# AMP_1_0.net
KiCad netlist of a schematic drawn in EAGLE
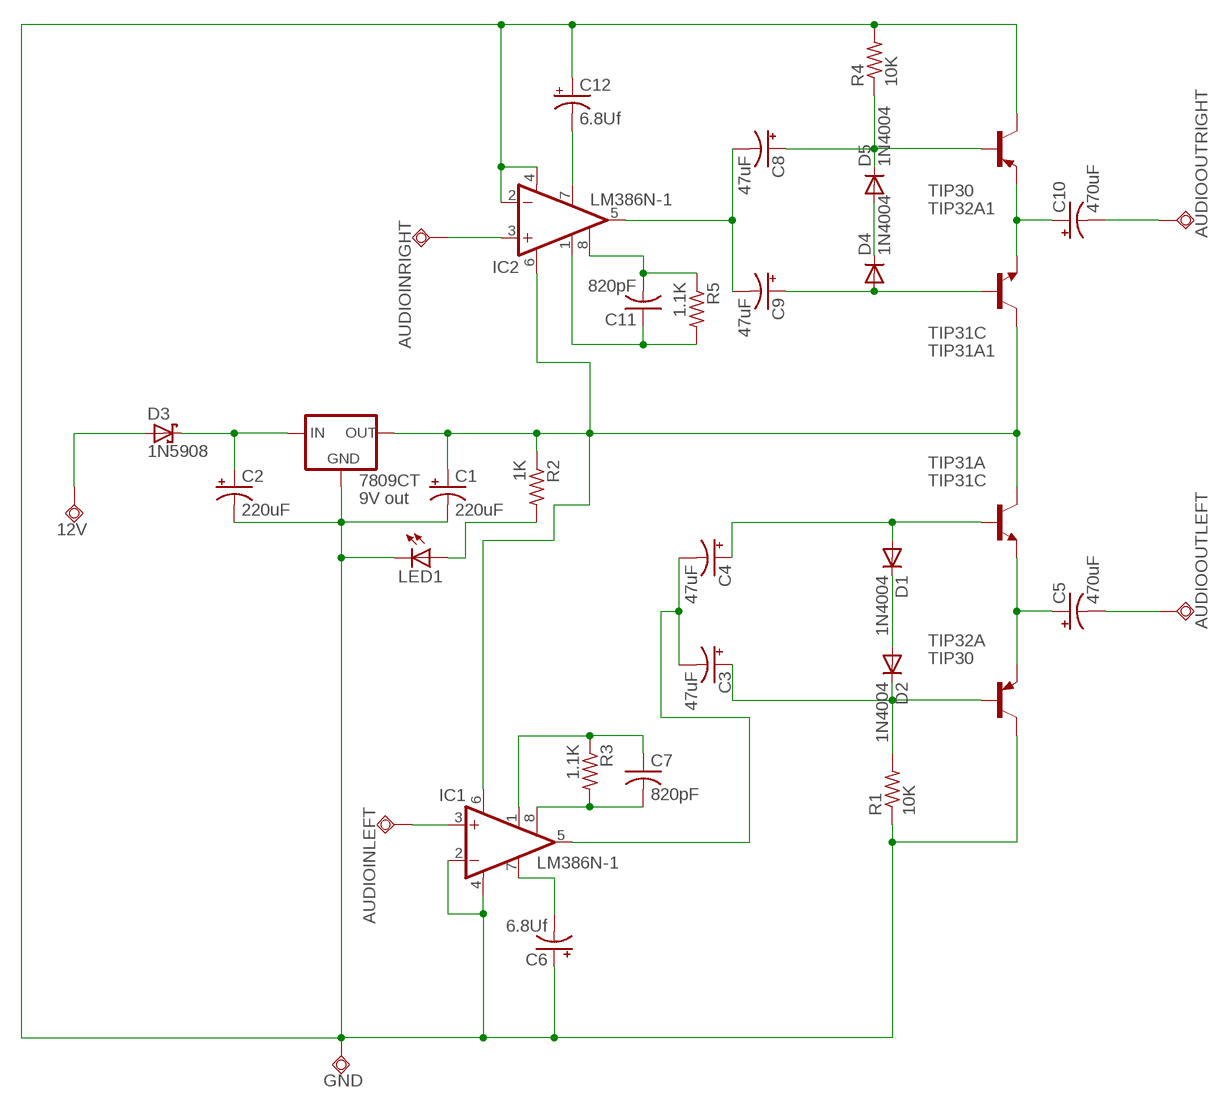
[diagram p0: schematic, sheet 1]

(export (version "E")
  (design (tool "Eeschema 10.0.6"))
  (components
    (comp (ref "12V")
      (value "TPSQPAD1-20")
      (footprint "eagle-import:P1-20")
      (libsource (lib "eagle-import") (part "TPSQPAD1-20"))
    )
    (comp (ref "7809CT")
      (value "9V out")
      (footprint "eagle-import:78XXL")
      (libsource (lib "eagle-import") (part "78XXL"))
    )
    (comp (ref "AUDIOINLEFT")
      (value "TPSQPAD1-20")
      (footprint "eagle-import:P1-20")
      (libsource (lib "eagle-import") (part "TPSQPAD1-20"))
    )
    (comp (ref "AUDIOINRIGHT")
      (value "TPSQPAD1-20")
      (footprint "eagle-import:P1-20")
      (libsource (lib "eagle-import") (part "TPSQPAD1-20"))
    )
    (comp (ref "AUDIOOUTLEFT")
      (value "TPSQPAD1-20")
      (footprint "eagle-import:P1-20")
      (libsource (lib "eagle-import") (part "TPSQPAD1-20"))
    )
    (comp (ref "AUDIOOUTRIGHT")
      (value "TPSQPAD1-20")
      (footprint "eagle-import:P1-20")
      (libsource (lib "eagle-import") (part "TPSQPAD1-20"))
    )
    (comp (ref "C1")
      (value "220uF")
      (footprint "eagle-import:B45181C")
      (libsource (lib "eagle-import") (part "CPOL-USB45181C"))
    )
    (comp (ref "C2")
      (value "220uF")
      (footprint "eagle-import:B45181C")
      (libsource (lib "eagle-import") (part "CPOL-USB45181C"))
    )
    (comp (ref "C3")
      (value "47uF")
      (footprint "eagle-import:E5-4")
      (libsource (lib "eagle-import") (part "CPOL-USE5-4"))
    )
    (comp (ref "C4")
      (value "47uF")
      (footprint "eagle-import:E5-4")
      (libsource (lib "eagle-import") (part "CPOL-USE5-4"))
    )
    (comp (ref "C5")
      (value "470uF")
      (footprint "eagle-import:E5-4")
      (libsource (lib "eagle-import") (part "CPOL-USE5-4"))
    )
    (comp (ref "C6")
      (value "6.8Uf")
      (footprint "eagle-import:E5-4")
      (libsource (lib "eagle-import") (part "CPOL-USE5-4"))
    )
    (comp (ref "C7")
      (value "820pF")
      (footprint "eagle-import:C050-050X075")
      (libsource (lib "eagle-import") (part "C-US050-050X075"))
    )
    (comp (ref "C8")
      (value "47uF")
      (footprint "eagle-import:E5-4")
      (libsource (lib "eagle-import") (part "CPOL-USE5-4"))
    )
    (comp (ref "C9")
      (value "47uF")
      (footprint "eagle-import:E5-4")
      (libsource (lib "eagle-import") (part "CPOL-USE5-4"))
    )
    (comp (ref "C10")
      (value "470uF")
      (footprint "eagle-import:E5-4")
      (libsource (lib "eagle-import") (part "CPOL-USE5-4"))
    )
    (comp (ref "C11")
      (value "820pF")
      (footprint "eagle-import:C050-050X075")
      (libsource (lib "eagle-import") (part "C-US050-050X075"))
    )
    (comp (ref "C12")
      (value "6.8Uf")
      (footprint "eagle-import:E5-4")
      (libsource (lib "eagle-import") (part "CPOL-USE5-4"))
    )
    (comp (ref "D1")
      (value "1N4004")
      (footprint "eagle-import:DO41-10")
      (libsource (lib "eagle-import") (part "1N4004"))
    )
    (comp (ref "D2")
      (value "1N4004")
      (footprint "eagle-import:DO41-10")
      (libsource (lib "eagle-import") (part "1N4004"))
    )
    (comp (ref "D3")
      (value "1N5908")
      (footprint "eagle-import:C4111-15")
      (libsource (lib "eagle-import") (part "1N5908"))
    )
    (comp (ref "D4")
      (value "1N4004")
      (footprint "eagle-import:DO41-10")
      (libsource (lib "eagle-import") (part "1N4004"))
    )
    (comp (ref "D5")
      (value "1N4004")
      (footprint "eagle-import:DO41-10")
      (libsource (lib "eagle-import") (part "1N4004"))
    )
    (comp (ref "GND")
      (value "TPSQPAD1-20")
      (footprint "eagle-import:P1-20")
      (libsource (lib "eagle-import") (part "TPSQPAD1-20"))
    )
    (comp (ref "IC1")
      (value "LM386N-1")
      (footprint "eagle-import:DIL08")
      (libsource (lib "eagle-import") (part "LM386?-N1"))
    )
    (comp (ref "IC2")
      (value "LM386N-1")
      (footprint "eagle-import:DIL08")
      (libsource (lib "eagle-import") (part "LM386?-N1"))
    )
    (comp (ref "LED1")
      (value "LED5MM")
      (footprint "eagle-import:LED5MM")
      (libsource (lib "eagle-import") (part "LED5MM"))
    )
    (comp (ref "R1")
      (value "10K")
      (footprint "eagle-import:0204_7")
      (libsource (lib "eagle-import") (part "R-US_0204/7"))
    )
    (comp (ref "R2")
      (value "1K")
      (footprint "eagle-import:0204_7")
      (libsource (lib "eagle-import") (part "R-US_0204/7"))
    )
    (comp (ref "R3")
      (value "1.1K")
      (footprint "eagle-import:0204_7")
      (libsource (lib "eagle-import") (part "R-US_0204/7"))
    )
    (comp (ref "R4")
      (value "10K")
      (footprint "eagle-import:0204_7")
      (libsource (lib "eagle-import") (part "R-US_0204/7"))
    )
    (comp (ref "R5")
      (value "1.1K")
      (footprint "eagle-import:0204_7")
      (libsource (lib "eagle-import") (part "R-US_0204/7"))
    )
    (comp (ref "TIP31A")
      (value "TIP31C")
      (footprint "eagle-import:TO220")
      (libsource (lib "eagle-import") (part "TIP31C"))
    )
    (comp (ref "TIP31A1")
      (value "TIP31C")
      (footprint "eagle-import:TO220")
      (libsource (lib "eagle-import") (part "TIP31C"))
    )
    (comp (ref "TIP32A")
      (value "TIP30")
      (footprint "eagle-import:TO220")
      (libsource (lib "eagle-import") (part "TIP30"))
    )
    (comp (ref "TIP32A1")
      (value "TIP30")
      (footprint "eagle-import:TO220")
      (libsource (lib "eagle-import") (part "TIP30"))
    )
  )
  (nets
    (net (code "1") (name "Net-(12V-PadTP)") (class "Default")
      (node (ref "12V") (pin "TP") (pinfunction "TP_TP") (pintype "input"))
      (node (ref "D3") (pin "A") (pinfunction "A_A") (pintype "passive"))
    )
    (net (code "2") (name "Net-(7809CT-PadIN)") (class "Default")
      (node (ref "7809CT") (pin "IN") (pinfunction "IN_IN") (pintype "input"))
      (node (ref "C2") (pin "+") (pinfunction "+_+") (pintype "passive"))
      (node (ref "D3") (pin "C") (pinfunction "C_C") (pintype "passive"))
    )
    (net (code "3") (name "Net-(AUDIOOUTLEFT-PadTP)") (class "Default")
      (node (ref "AUDIOOUTLEFT") (pin "TP") (pinfunction "TP_TP") (pintype "input"))
      (node (ref "C5") (pin "-") (pinfunction "-_-") (pintype "passive"))
    )
    (net (code "4") (name "Net-(AUDIOOUTRIGHT-PadTP)") (class "Default")
      (node (ref "AUDIOOUTRIGHT") (pin "TP") (pinfunction "TP_TP") (pintype "input"))
      (node (ref "C10") (pin "-") (pinfunction "-_-") (pintype "passive"))
    )
    (net (code "5") (name "Net-(C7-Pad1)") (class "Default")
      (node (ref "C7") (pin "1") (pinfunction "1_1") (pintype "passive"))
      (node (ref "IC1") (pin "1") (pinfunction "GAIN_1") (pintype "passive"))
      (node (ref "R3") (pin "1") (pinfunction "1_1") (pintype "passive"))
    )
    (net (code "6") (name "Net-(C7-Pad2)") (class "Default")
      (node (ref "C7") (pin "2") (pinfunction "2_2") (pintype "passive"))
      (node (ref "IC1") (pin "8") (pinfunction "GAIN_8") (pintype "passive"))
      (node (ref "R3") (pin "2") (pinfunction "2_2") (pintype "passive"))
    )
    (net (code "7") (name "Net-(C11-Pad1)") (class "Default")
      (node (ref "C11") (pin "1") (pinfunction "1_1") (pintype "passive"))
      (node (ref "IC2") (pin "1") (pinfunction "GAIN_1") (pintype "passive"))
      (node (ref "R5") (pin "2") (pinfunction "2_2") (pintype "passive"))
    )
    (net (code "8") (name "Net-(C11-Pad2)") (class "Default")
      (node (ref "C11") (pin "2") (pinfunction "2_2") (pintype "passive"))
      (node (ref "IC2") (pin "8") (pinfunction "GAIN_8") (pintype "passive"))
      (node (ref "R5") (pin "1") (pinfunction "1_1") (pintype "passive"))
    )
    (net (code "9") (name "Net-(D1-PadC)") (class "Default")
      (node (ref "D1") (pin "C") (pinfunction "C_C") (pintype "passive"))
      (node (ref "D2") (pin "A") (pinfunction "A_A") (pintype "passive"))
    )
    (net (code "10") (name "Net-(D4-PadC)") (class "Default")
      (node (ref "D4") (pin "C") (pinfunction "C_C") (pintype "passive"))
      (node (ref "D5") (pin "A") (pinfunction "A_A") (pintype "passive"))
    )
    (net (code "11") (name "Net-(IC1-+IN)") (class "Default")
      (node (ref "AUDIOINLEFT") (pin "TP") (pinfunction "TP_TP") (pintype "input"))
      (node (ref "IC1") (pin "3") (pinfunction "+IN_3") (pintype "input"))
    )
    (net (code "12") (name "Net-(IC1--IN)") (class "Default")
      (node (ref "7809CT") (pin "GND") (pinfunction "GND_GND") (pintype "input"))
      (node (ref "C1") (pin "-") (pinfunction "-_-") (pintype "passive"))
      (node (ref "C12") (pin "+") (pinfunction "+_+") (pintype "passive"))
      (node (ref "C2") (pin "-") (pinfunction "-_-") (pintype "passive"))
      (node (ref "C6") (pin "+") (pinfunction "+_+") (pintype "passive"))
      (node (ref "GND") (pin "TP") (pinfunction "TP_TP") (pintype "input"))
      (node (ref "IC1") (pin "2") (pinfunction "-IN_2") (pintype "input"))
      (node (ref "IC1") (pin "4") (pinfunction "GND_4") (pintype "power_in"))
      (node (ref "IC2") (pin "2") (pinfunction "-IN_2") (pintype "input"))
      (node (ref "IC2") (pin "4") (pinfunction "GND_4") (pintype "power_in"))
      (node (ref "LED1") (pin "K") (pinfunction "C_K") (pintype "passive"))
      (node (ref "R1") (pin "1") (pinfunction "1_1") (pintype "passive"))
      (node (ref "R4") (pin "2") (pinfunction "2_2") (pintype "passive"))
      (node (ref "TIP32A") (pin "2") (pinfunction "C_2") (pintype "passive"))
      (node (ref "TIP32A1") (pin "2") (pinfunction "C_2") (pintype "passive"))
    )
    (net (code "13") (name "Net-(IC1-BYPASS)") (class "Default")
      (node (ref "C6") (pin "-") (pinfunction "-_-") (pintype "passive"))
      (node (ref "IC1") (pin "7") (pinfunction "BYPASS_7") (pintype "passive"))
    )
    (net (code "14") (name "Net-(IC1-OUT)") (class "Default")
      (node (ref "C3") (pin "-") (pinfunction "-_-") (pintype "passive"))
      (node (ref "C4") (pin "-") (pinfunction "-_-") (pintype "passive"))
      (node (ref "IC1") (pin "5") (pinfunction "OUT_5") (pintype "output"))
    )
    (net (code "15") (name "Net-(IC1-VS)") (class "Default")
      (node (ref "7809CT") (pin "OUT") (pinfunction "OUT_OUT") (pintype "passive"))
      (node (ref "C1") (pin "+") (pinfunction "+_+") (pintype "passive"))
      (node (ref "IC1") (pin "6") (pinfunction "VS_6") (pintype "power_in"))
      (node (ref "IC2") (pin "6") (pinfunction "VS_6") (pintype "power_in"))
      (node (ref "R2") (pin "1") (pinfunction "1_1") (pintype "passive"))
      (node (ref "TIP31A") (pin "2") (pinfunction "C_2") (pintype "passive"))
      (node (ref "TIP31A1") (pin "2") (pinfunction "C_2") (pintype "passive"))
    )
    (net (code "16") (name "Net-(IC2-+IN)") (class "Default")
      (node (ref "AUDIOINRIGHT") (pin "TP") (pinfunction "TP_TP") (pintype "input"))
      (node (ref "IC2") (pin "3") (pinfunction "+IN_3") (pintype "input"))
    )
    (net (code "17") (name "Net-(IC2-BYPASS)") (class "Default")
      (node (ref "C12") (pin "-") (pinfunction "-_-") (pintype "passive"))
      (node (ref "IC2") (pin "7") (pinfunction "BYPASS_7") (pintype "passive"))
    )
    (net (code "18") (name "Net-(IC2-OUT)") (class "Default")
      (node (ref "C8") (pin "-") (pinfunction "-_-") (pintype "passive"))
      (node (ref "C9") (pin "-") (pinfunction "-_-") (pintype "passive"))
      (node (ref "IC2") (pin "5") (pinfunction "OUT_5") (pintype "output"))
    )
    (net (code "19") (name "Net-(LED1-PadA)") (class "Default")
      (node (ref "LED1") (pin "A") (pinfunction "A_A") (pintype "passive"))
      (node (ref "R2") (pin "2") (pinfunction "2_2") (pintype "passive"))
    )
    (net (code "20") (name "Net-(TIP31A-B)") (class "Default")
      (node (ref "C4") (pin "+") (pinfunction "+_+") (pintype "passive"))
      (node (ref "D1") (pin "A") (pinfunction "A_A") (pintype "passive"))
      (node (ref "TIP31A") (pin "1") (pinfunction "B_1") (pintype "passive"))
    )
    (net (code "21") (name "Net-(TIP31A-E)") (class "Default")
      (node (ref "C5") (pin "+") (pinfunction "+_+") (pintype "passive"))
      (node (ref "TIP31A") (pin "3") (pinfunction "E_3") (pintype "passive"))
      (node (ref "TIP32A") (pin "3") (pinfunction "E_3") (pintype "passive"))
    )
    (net (code "22") (name "Net-(TIP31A1-B)") (class "Default")
      (node (ref "C9") (pin "+") (pinfunction "+_+") (pintype "passive"))
      (node (ref "D4") (pin "A") (pinfunction "A_A") (pintype "passive"))
      (node (ref "TIP31A1") (pin "1") (pinfunction "B_1") (pintype "passive"))
    )
    (net (code "23") (name "Net-(TIP31A1-E)") (class "Default")
      (node (ref "C10") (pin "+") (pinfunction "+_+") (pintype "passive"))
      (node (ref "TIP31A1") (pin "3") (pinfunction "E_3") (pintype "passive"))
      (node (ref "TIP32A1") (pin "3") (pinfunction "E_3") (pintype "passive"))
    )
    (net (code "24") (name "Net-(TIP32A-B)") (class "Default")
      (node (ref "C3") (pin "+") (pinfunction "+_+") (pintype "passive"))
      (node (ref "D2") (pin "C") (pinfunction "C_C") (pintype "passive"))
      (node (ref "R1") (pin "2") (pinfunction "2_2") (pintype "passive"))
      (node (ref "TIP32A") (pin "1") (pinfunction "B_1") (pintype "passive"))
    )
    (net (code "25") (name "Net-(TIP32A1-B)") (class "Default")
      (node (ref "C8") (pin "+") (pinfunction "+_+") (pintype "passive"))
      (node (ref "D5") (pin "C") (pinfunction "C_C") (pintype "passive"))
      (node (ref "R4") (pin "1") (pinfunction "1_1") (pintype "passive"))
      (node (ref "TIP32A1") (pin "1") (pinfunction "B_1") (pintype "passive"))
    )
  )
)
